# easy_001.net
KiCad netlist of a schematic drawn in EAGLE
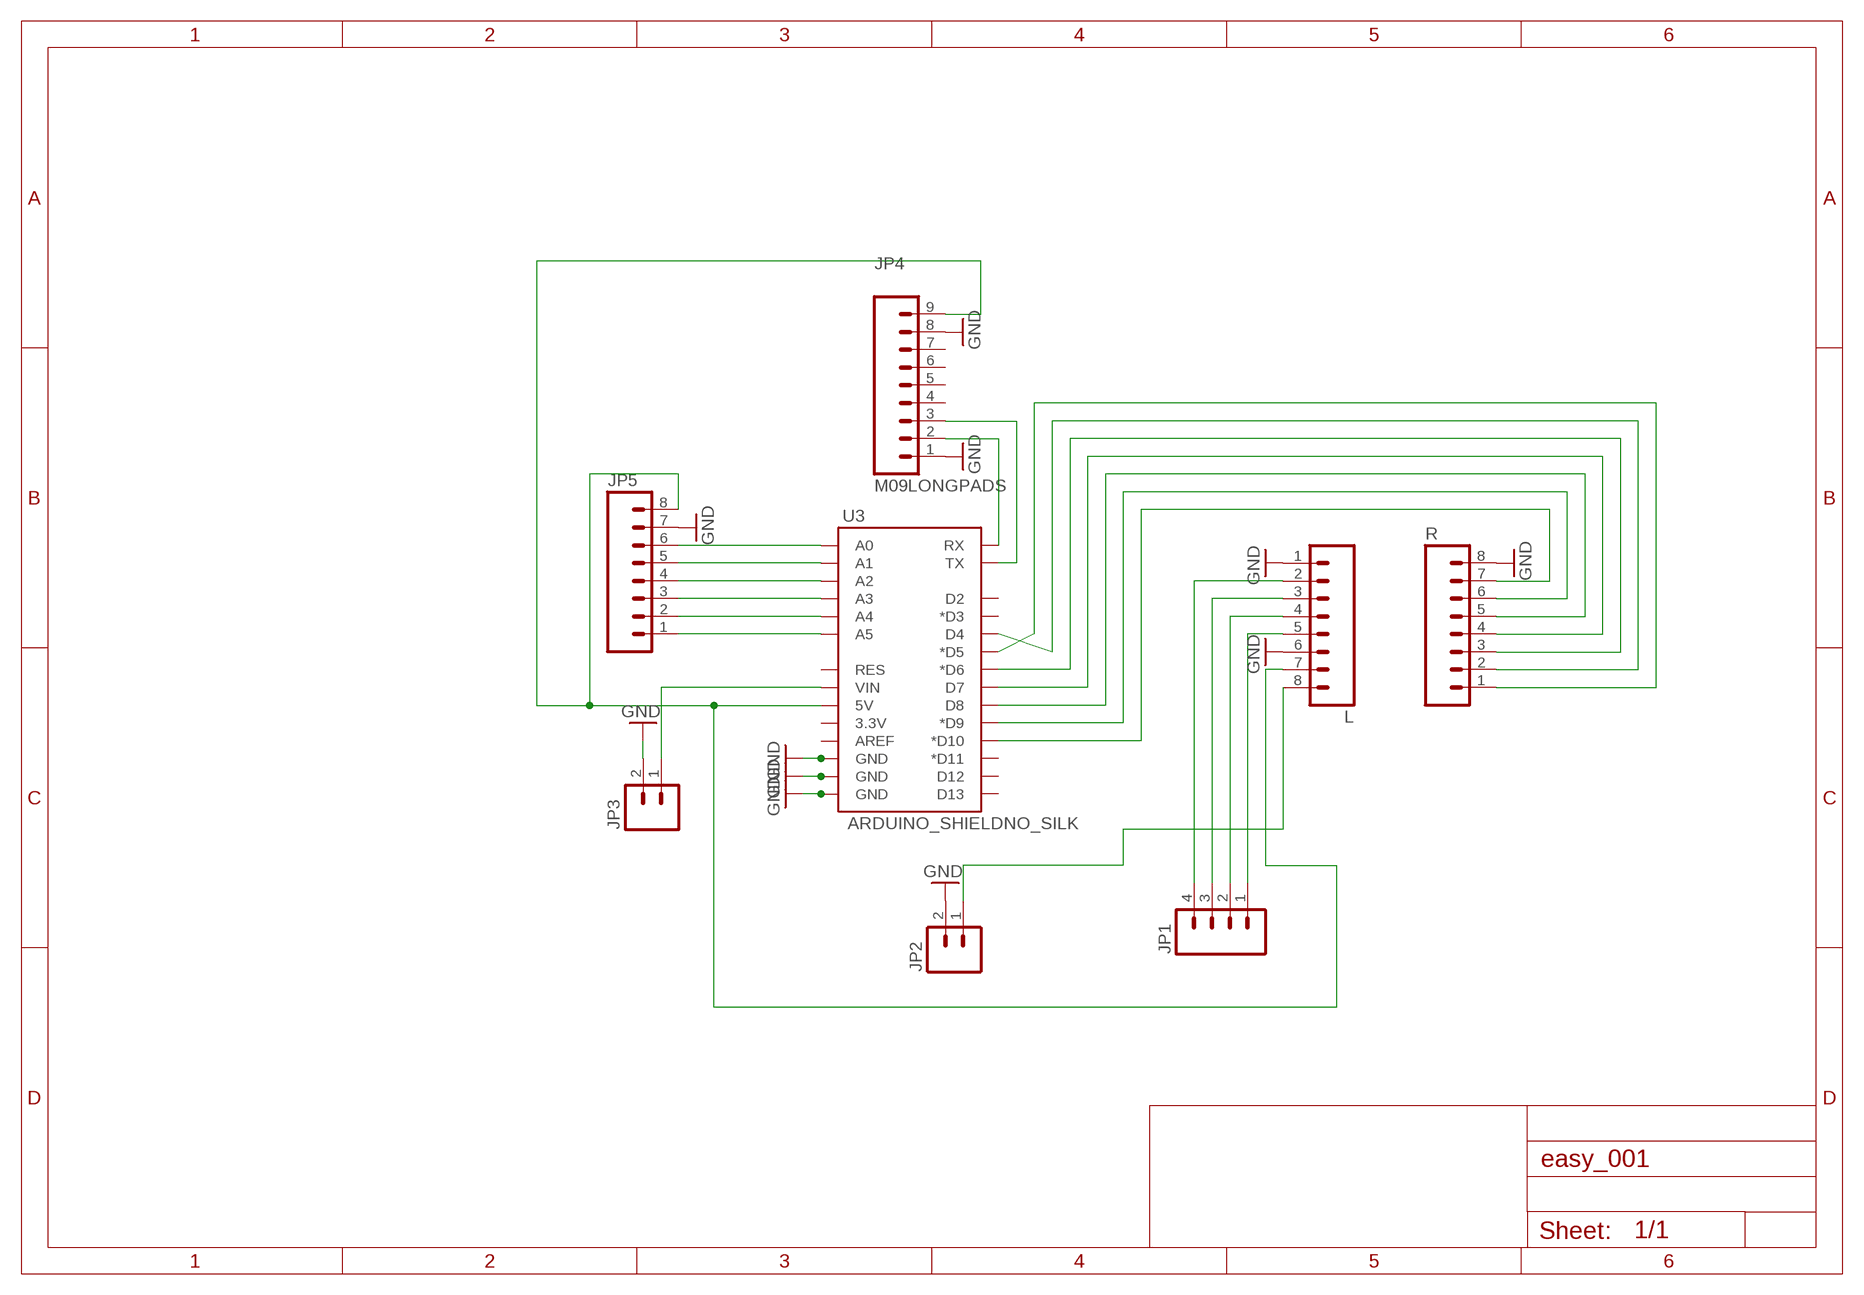
[diagram p0: schematic, sheet 1]

(export (version "E")
  (design (tool "Eeschema 10.0.6"))
  (components
    (comp (ref "JP1")
      (value "M04LONGPADS")
      (footprint "eagle-import:1X04_LONGPADS")
      (libsource (lib "eagle-import") (part "M04LONGPADS"))
    )
    (comp (ref "JP2")
      (value "M02PTH3")
      (footprint "eagle-import:1X02_LONGPADS")
      (libsource (lib "eagle-import") (part "M02PTH3"))
    )
    (comp (ref "JP3")
      (value "M02PTH3")
      (footprint "eagle-import:1X02_LONGPADS")
      (libsource (lib "eagle-import") (part "M02PTH3"))
    )
    (comp (ref "JP4")
      (value "M09LONGPADS")
      (footprint "eagle-import:1X09_LONGPADS")
      (libsource (lib "eagle-import") (part "M09LONGPADS"))
    )
    (comp (ref "JP5")
      (value "M08LONGPADS")
      (footprint "eagle-import:1X08_LONGPADS")
      (libsource (lib "eagle-import") (part "SparkFun-Connectors_M08LONGPADS"))
    )
    (comp (ref "L")
      (value "M08LONGPADS")
      (footprint "eagle-import:1X08_LONGPADS")
      (libsource (lib "eagle-import") (part "M08LONGPADS"))
    )
    (comp (ref "R")
      (value "M08LONGPADS")
      (footprint "eagle-import:1X08_LONGPADS")
      (libsource (lib "eagle-import") (part "M08LONGPADS"))
    )
    (comp (ref "U3")
      (value "ARDUINO_SHIELDNO_SILK")
      (footprint "eagle-import:DUEMILANOVE_VIAS")
      (libsource (lib "eagle-import") (part "ARDUINO_SHIELDNO_SILK"))
    )
  )
  (nets
    (net (code "1") (name "GND") (class "Default")
      (node (ref "JP2") (pin "2") (pinfunction "2_2") (pintype "passive"))
      (node (ref "JP3") (pin "2") (pinfunction "2_2") (pintype "passive"))
      (node (ref "JP4") (pin "1") (pinfunction "1_1") (pintype "passive"))
      (node (ref "JP4") (pin "8") (pinfunction "8_8") (pintype "passive"))
      (node (ref "JP5") (pin "7") (pinfunction "7_7") (pintype "passive"))
      (node (ref "L") (pin "1") (pinfunction "1_1") (pintype "passive"))
      (node (ref "L") (pin "6") (pinfunction "6_6") (pintype "passive"))
      (node (ref "R") (pin "8") (pinfunction "8_8") (pintype "passive"))
      (node (ref "U3") (pin "GND@0") (pinfunction "GND_GND@0") (pintype "bidirectional"))
      (node (ref "U3") (pin "GND@1") (pinfunction "GND_GND@1") (pintype "bidirectional"))
      (node (ref "U3") (pin "GND@2") (pinfunction "GND_GND@2") (pintype "bidirectional"))
    )
    (net (code "2") (name "Net-(JP1-Pad1)") (class "Default")
      (node (ref "JP1") (pin "1") (pinfunction "1_1") (pintype "passive"))
      (node (ref "L") (pin "5") (pinfunction "5_5") (pintype "passive"))
    )
    (net (code "3") (name "Net-(JP1-Pad2)") (class "Default")
      (node (ref "JP1") (pin "2") (pinfunction "2_2") (pintype "passive"))
      (node (ref "L") (pin "4") (pinfunction "4_4") (pintype "passive"))
    )
    (net (code "4") (name "Net-(JP1-Pad3)") (class "Default")
      (node (ref "JP1") (pin "3") (pinfunction "3_3") (pintype "passive"))
      (node (ref "L") (pin "3") (pinfunction "3_3") (pintype "passive"))
    )
    (net (code "5") (name "Net-(JP1-Pad4)") (class "Default")
      (node (ref "JP1") (pin "4") (pinfunction "4_4") (pintype "passive"))
      (node (ref "L") (pin "2") (pinfunction "2_2") (pintype "passive"))
    )
    (net (code "6") (name "Net-(JP2-Pad1)") (class "Default")
      (node (ref "JP2") (pin "1") (pinfunction "1_1") (pintype "passive"))
      (node (ref "L") (pin "8") (pinfunction "8_8") (pintype "passive"))
    )
    (net (code "7") (name "Net-(JP3-Pad1)") (class "Default")
      (node (ref "JP3") (pin "1") (pinfunction "1_1") (pintype "passive"))
      (node (ref "U3") (pin "VIN") (pinfunction "VIN_VIN") (pintype "bidirectional"))
    )
    (net (code "8") (name "Net-(JP4-Pad2)") (class "Default")
      (node (ref "JP4") (pin "2") (pinfunction "2_2") (pintype "passive"))
      (node (ref "U3") (pin "RX") (pinfunction "RX_RX") (pintype "bidirectional"))
    )
    (net (code "9") (name "Net-(JP4-Pad3)") (class "Default")
      (node (ref "JP4") (pin "3") (pinfunction "3_3") (pintype "passive"))
      (node (ref "U3") (pin "TX") (pinfunction "TX_TX") (pintype "bidirectional"))
    )
    (net (code "10") (name "Net-(JP4-Pad9)") (class "Default")
      (node (ref "JP4") (pin "9") (pinfunction "9_9") (pintype "passive"))
      (node (ref "JP5") (pin "8") (pinfunction "8_8") (pintype "passive"))
      (node (ref "L") (pin "7") (pinfunction "7_7") (pintype "passive"))
      (node (ref "U3") (pin "5V") (pinfunction "5V_5V") (pintype "bidirectional"))
    )
    (net (code "11") (name "Net-(JP5-Pad1)") (class "Default")
      (node (ref "JP5") (pin "1") (pinfunction "1_1") (pintype "passive"))
      (node (ref "U3") (pin "A5") (pinfunction "A5_A5") (pintype "bidirectional"))
    )
    (net (code "12") (name "Net-(JP5-Pad2)") (class "Default")
      (node (ref "JP5") (pin "2") (pinfunction "2_2") (pintype "passive"))
      (node (ref "U3") (pin "A4") (pinfunction "A4_A4") (pintype "bidirectional"))
    )
    (net (code "13") (name "Net-(JP5-Pad3)") (class "Default")
      (node (ref "JP5") (pin "3") (pinfunction "3_3") (pintype "passive"))
      (node (ref "U3") (pin "A3") (pinfunction "A3_A3") (pintype "bidirectional"))
    )
    (net (code "14") (name "Net-(JP5-Pad4)") (class "Default")
      (node (ref "JP5") (pin "4") (pinfunction "4_4") (pintype "passive"))
      (node (ref "U3") (pin "A2") (pinfunction "A2_A2") (pintype "bidirectional"))
    )
    (net (code "15") (name "Net-(JP5-Pad5)") (class "Default")
      (node (ref "JP5") (pin "5") (pinfunction "5_5") (pintype "passive"))
      (node (ref "U3") (pin "A1") (pinfunction "A1_A1") (pintype "bidirectional"))
    )
    (net (code "16") (name "Net-(JP5-Pad6)") (class "Default")
      (node (ref "JP5") (pin "6") (pinfunction "6_6") (pintype "passive"))
      (node (ref "U3") (pin "A0") (pinfunction "A0_A0") (pintype "bidirectional"))
    )
    (net (code "17") (name "Net-(R-Pad2)") (class "Default")
      (node (ref "R") (pin "2") (pinfunction "2_2") (pintype "passive"))
      (node (ref "U3") (pin "D4") (pinfunction "D4_D4") (pintype "bidirectional"))
    )
    (net (code "18") (name "Net-(R-Pad4)") (class "Default")
      (node (ref "R") (pin "4") (pinfunction "4_4") (pintype "passive"))
      (node (ref "U3") (pin "D7") (pinfunction "D7_D7") (pintype "bidirectional"))
    )
    (net (code "19") (name "Net-(R-Pad5)") (class "Default")
      (node (ref "R") (pin "5") (pinfunction "5_5") (pintype "passive"))
      (node (ref "U3") (pin "D8") (pinfunction "D8_D8") (pintype "bidirectional"))
    )
    (net (code "20") (name "Net-(U3-*D5)") (class "Default")
      (node (ref "R") (pin "1") (pinfunction "1_1") (pintype "passive"))
      (node (ref "U3") (pin "D5") (pinfunction "*D5_D5") (pintype "bidirectional"))
    )
    (net (code "21") (name "Net-(U3-*D6)") (class "Default")
      (node (ref "R") (pin "3") (pinfunction "3_3") (pintype "passive"))
      (node (ref "U3") (pin "D6") (pinfunction "*D6_D6") (pintype "bidirectional"))
    )
    (net (code "22") (name "Net-(U3-*D9)") (class "Default")
      (node (ref "R") (pin "6") (pinfunction "6_6") (pintype "passive"))
      (node (ref "U3") (pin "D9") (pinfunction "*D9_D9") (pintype "bidirectional"))
    )
    (net (code "23") (name "Net-(U3-*D10)") (class "Default")
      (node (ref "R") (pin "7") (pinfunction "7_7") (pintype "passive"))
      (node (ref "U3") (pin "D10") (pinfunction "*D10_D10") (pintype "bidirectional"))
    )
    (net (code "24") (name "unconnected-(JP4-Pad4)") (class "Default")
      (node (ref "JP4") (pin "4") (pinfunction "4_4") (pintype "passive"))
    )
    (net (code "25") (name "unconnected-(JP4-Pad5)") (class "Default")
      (node (ref "JP4") (pin "5") (pinfunction "5_5") (pintype "passive"))
    )
    (net (code "26") (name "unconnected-(JP4-Pad6)") (class "Default")
      (node (ref "JP4") (pin "6") (pinfunction "6_6") (pintype "passive"))
    )
    (net (code "27") (name "unconnected-(JP4-Pad7)") (class "Default")
      (node (ref "JP4") (pin "7") (pinfunction "7_7") (pintype "passive"))
    )
    (net (code "28") (name "unconnected-(U3-*D3-PadD3)") (class "Default")
      (node (ref "U3") (pin "D3") (pinfunction "*D3_D3") (pintype "bidirectional"))
    )
    (net (code "29") (name "unconnected-(U3-*D11-PadD11)") (class "Default")
      (node (ref "U3") (pin "D11") (pinfunction "*D11_D11") (pintype "bidirectional"))
    )
    (net (code "30") (name "unconnected-(U3-Pad3.3V)") (class "Default")
      (node (ref "U3") (pin "3.3V") (pinfunction "3.3V_3.3V") (pintype "bidirectional"))
    )
    (net (code "31") (name "unconnected-(U3-PadAREF)") (class "Default")
      (node (ref "U3") (pin "AREF") (pinfunction "AREF_AREF") (pintype "bidirectional"))
    )
    (net (code "32") (name "unconnected-(U3-PadD2)") (class "Default")
      (node (ref "U3") (pin "D2") (pinfunction "D2_D2") (pintype "bidirectional"))
    )
    (net (code "33") (name "unconnected-(U3-PadD12)") (class "Default")
      (node (ref "U3") (pin "D12") (pinfunction "D12_D12") (pintype "bidirectional"))
    )
    (net (code "34") (name "unconnected-(U3-PadD13)") (class "Default")
      (node (ref "U3") (pin "D13") (pinfunction "D13_D13") (pintype "bidirectional"))
    )
    (net (code "35") (name "unconnected-(U3-PadRES)") (class "Default")
      (node (ref "U3") (pin "RES") (pinfunction "RES_RES") (pintype "bidirectional"))
    )
  )
)
